# telakone-aux-gps.net
KiCad netlist of a schematic drawn in EAGLE
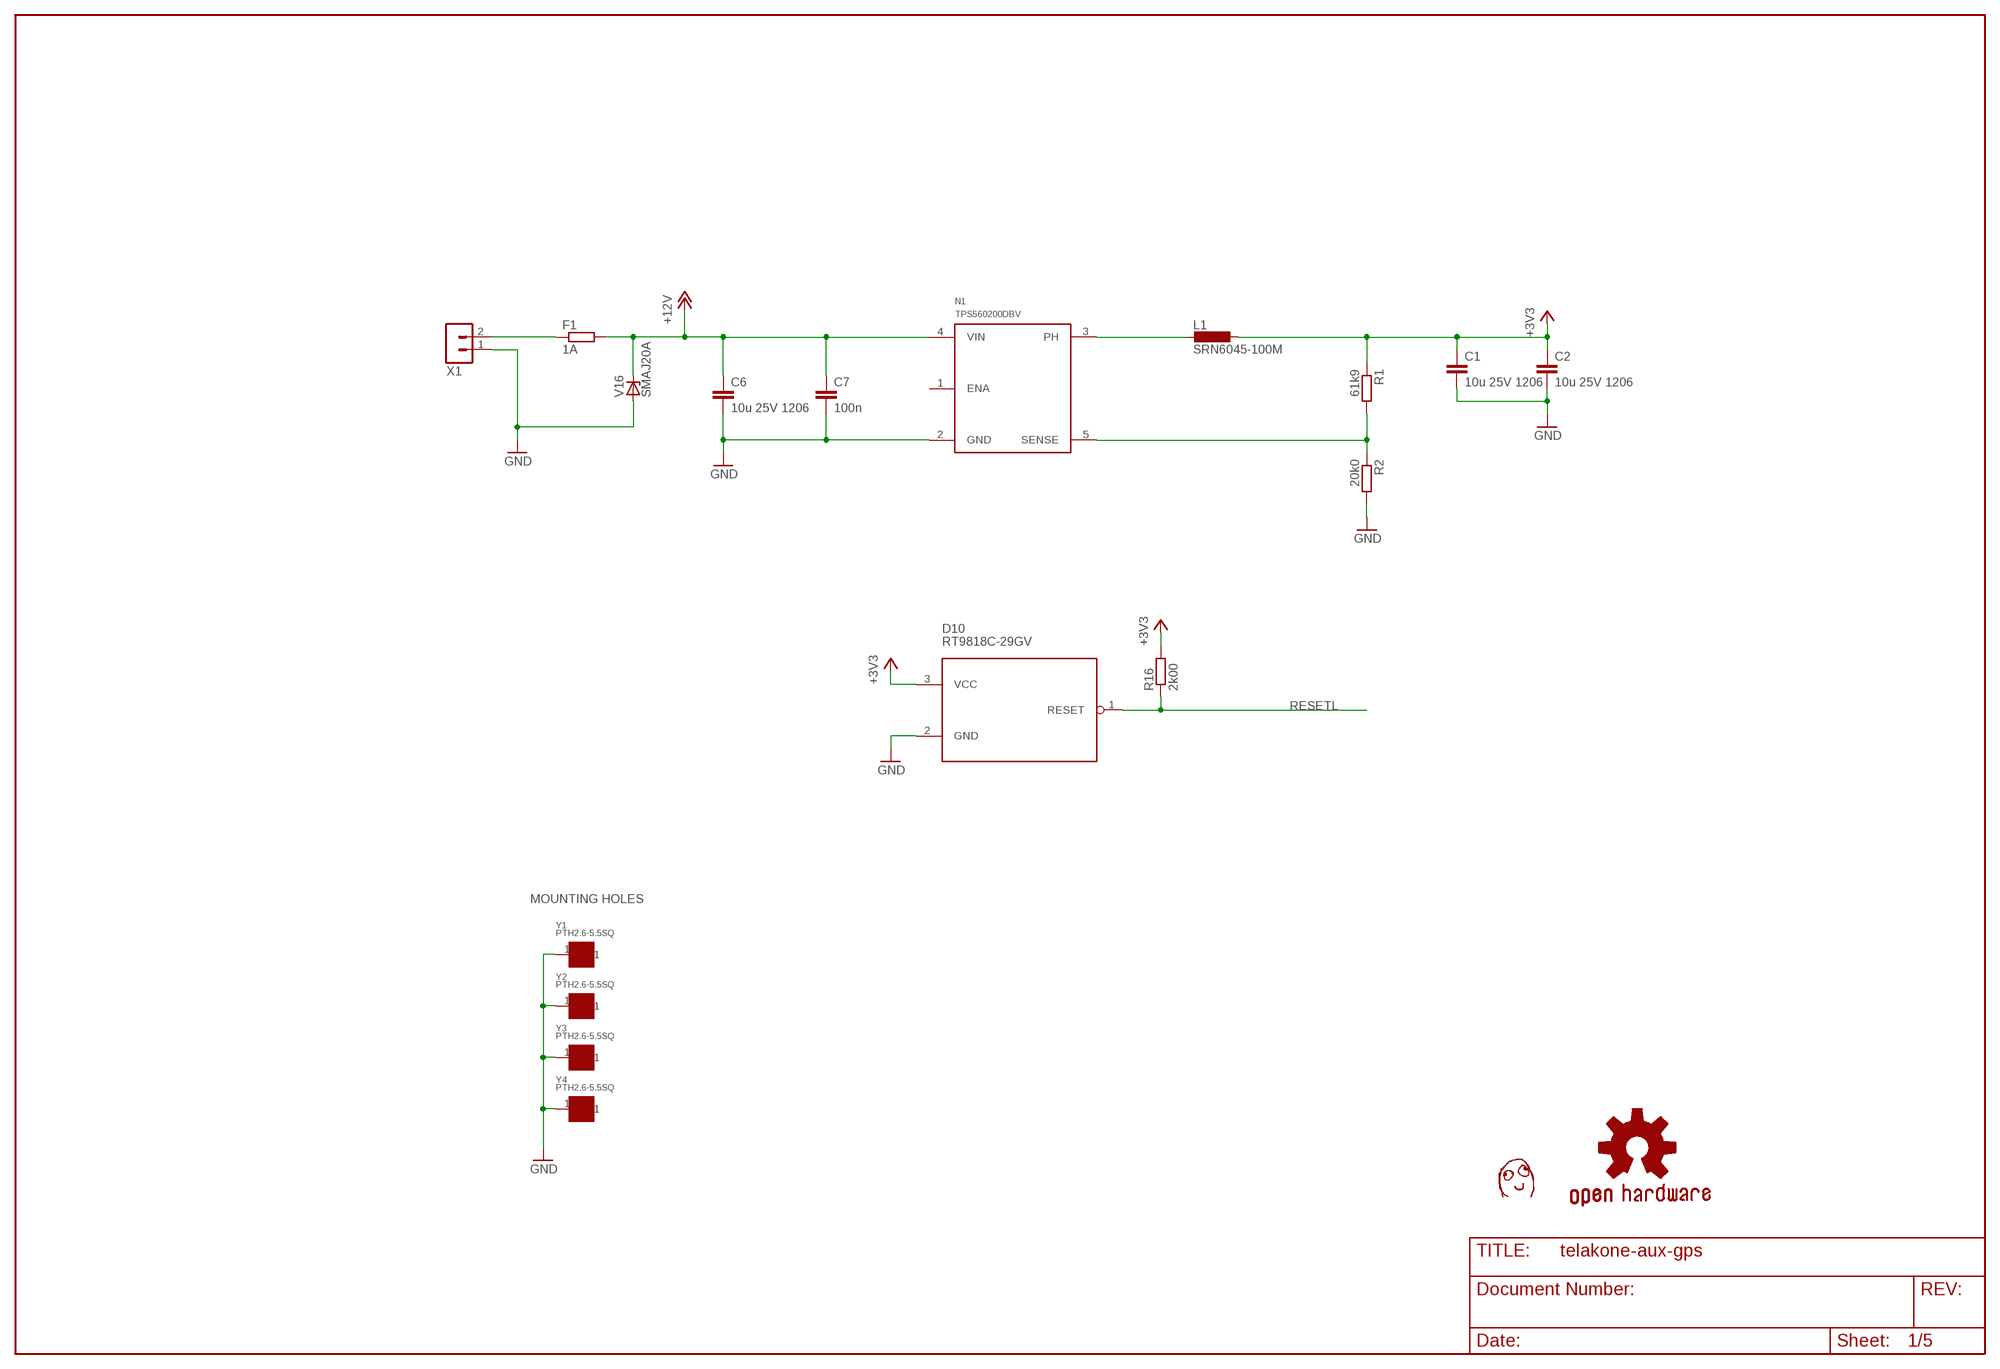
[diagram p0: schematic, sheet 1]
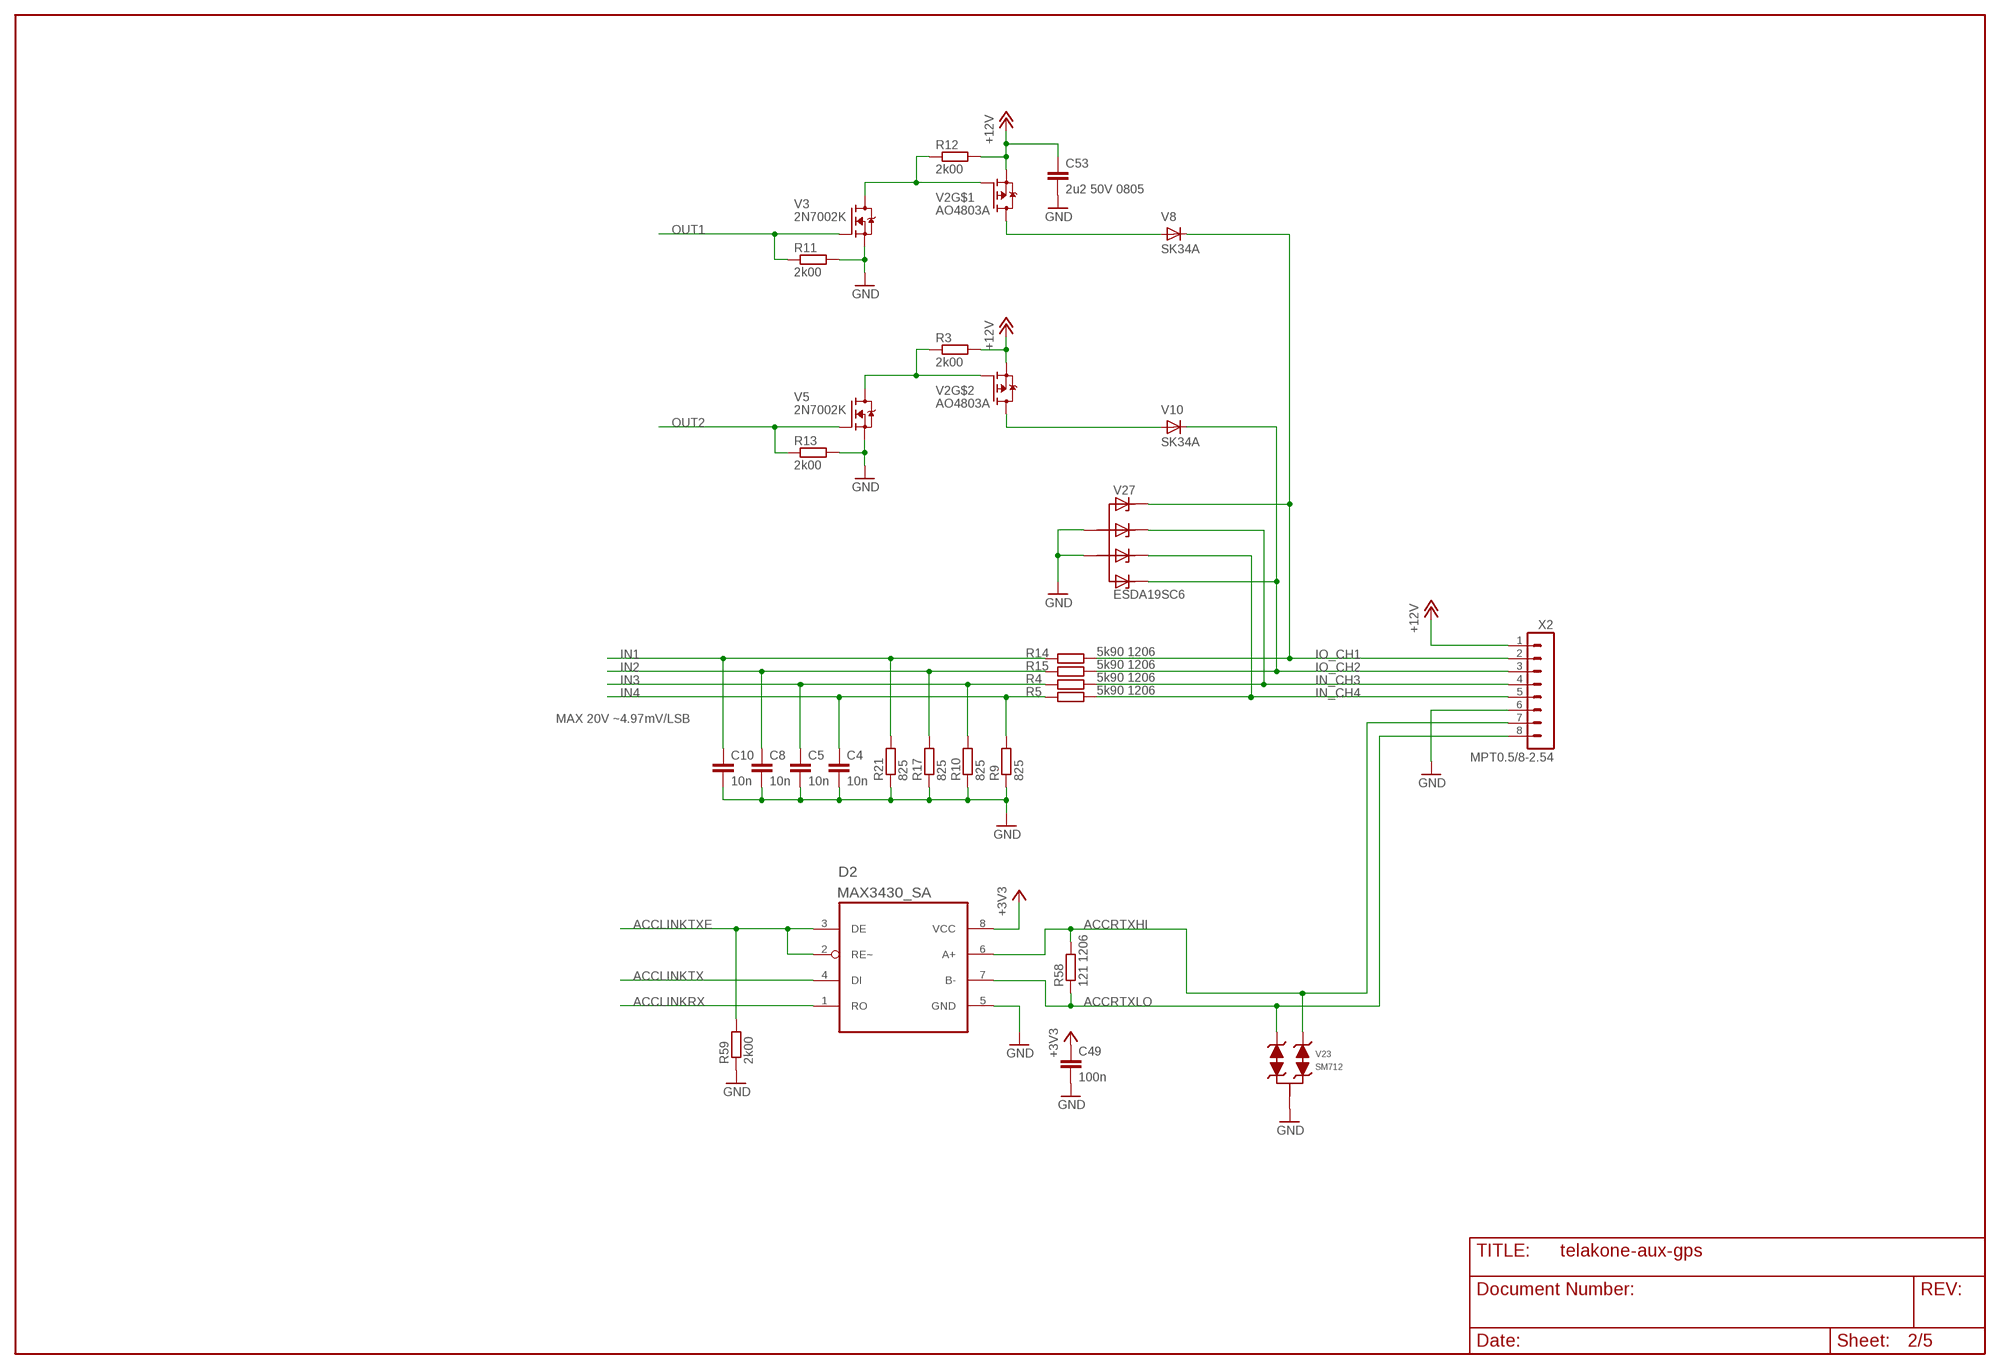
[diagram p1: schematic, sheet 2]
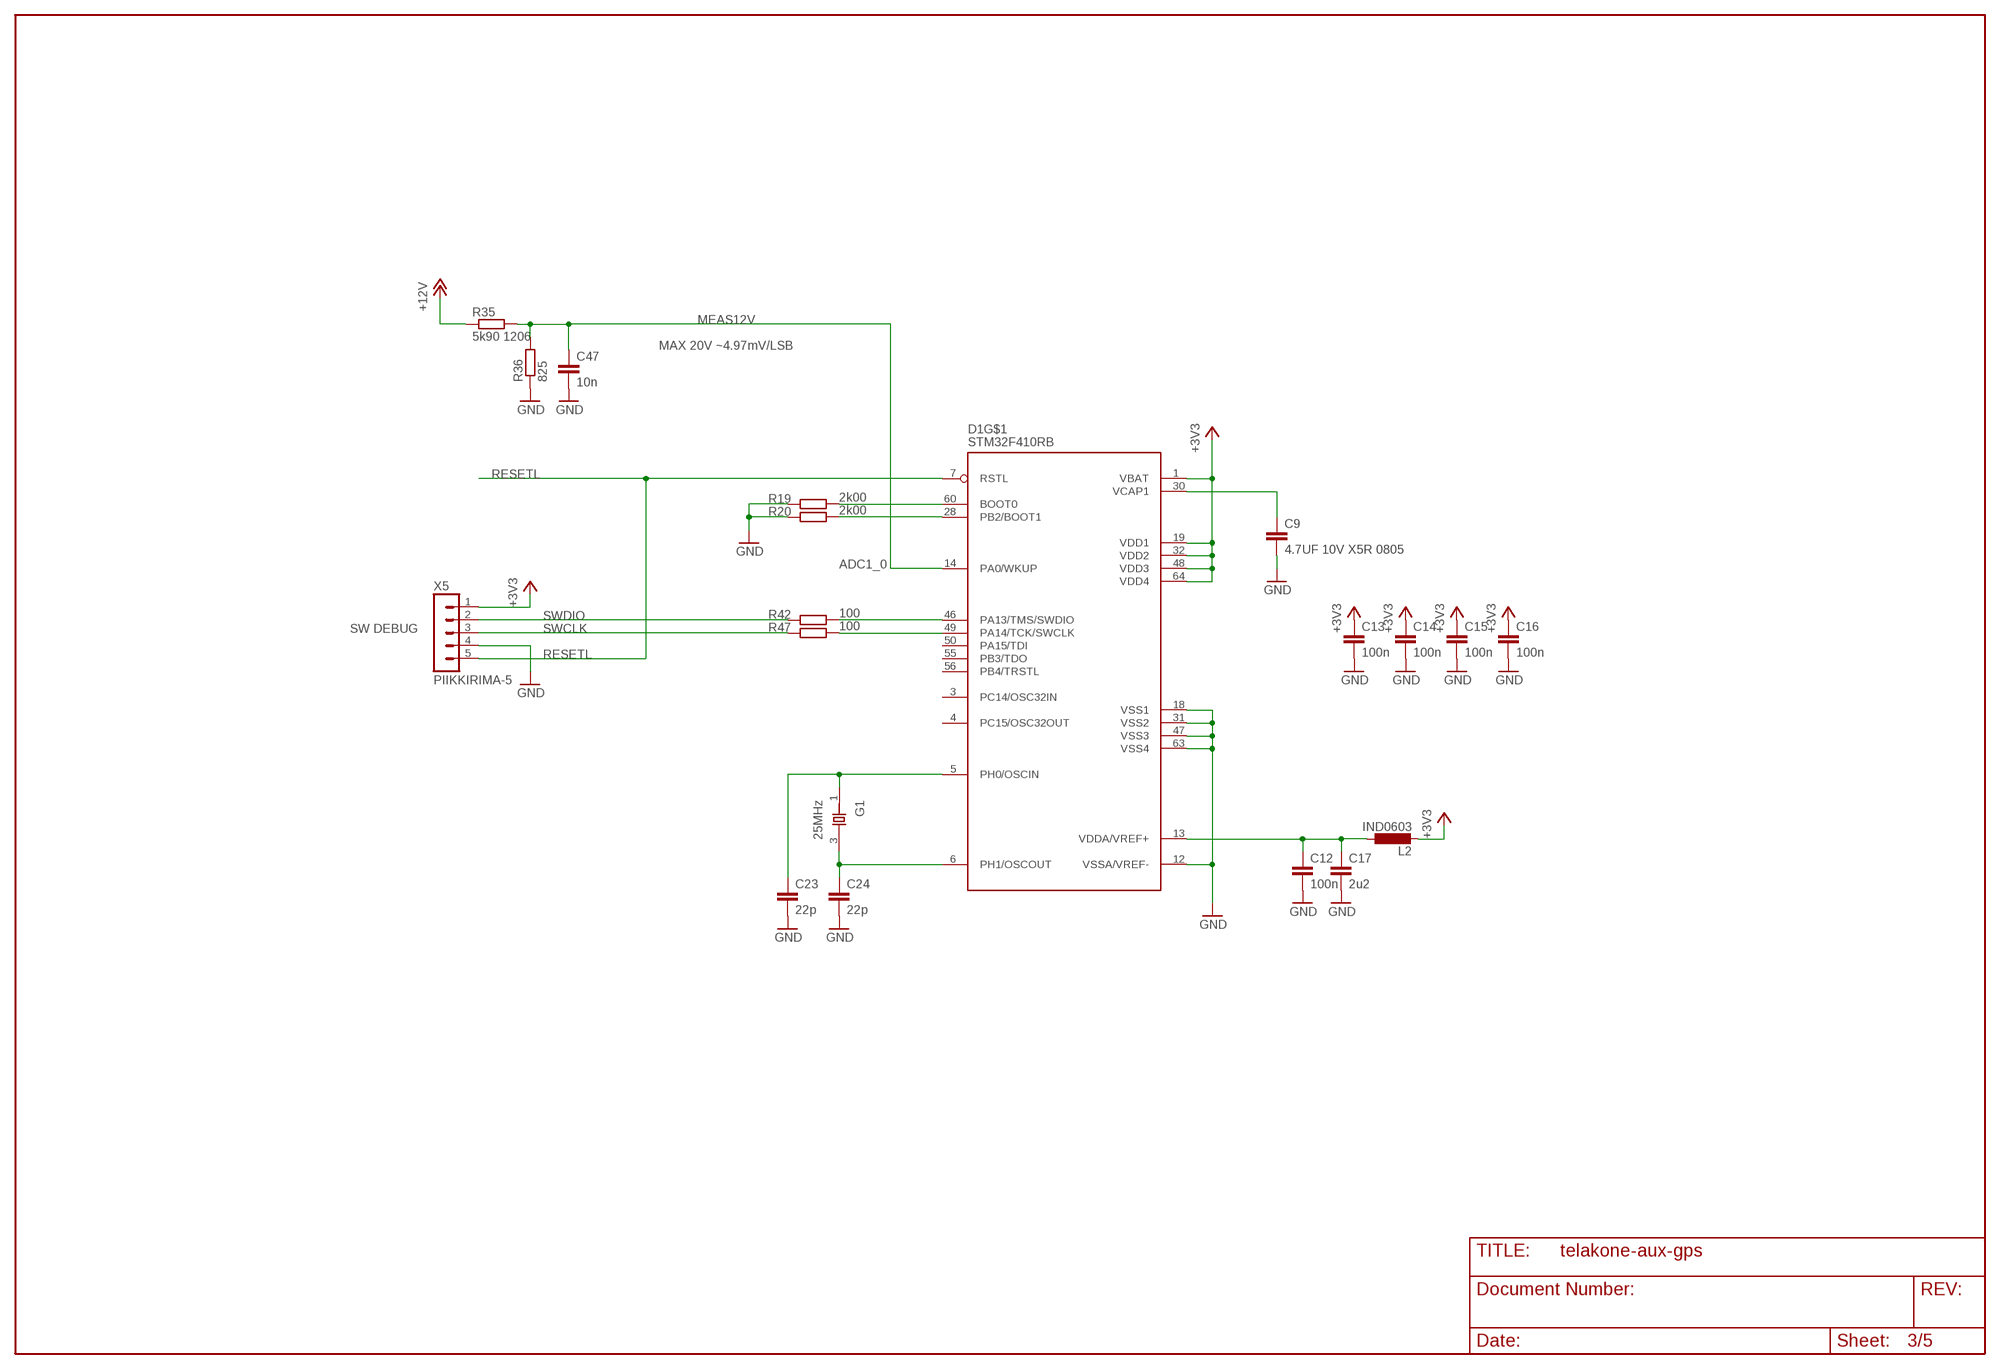
[diagram p2: schematic, sheet 3]
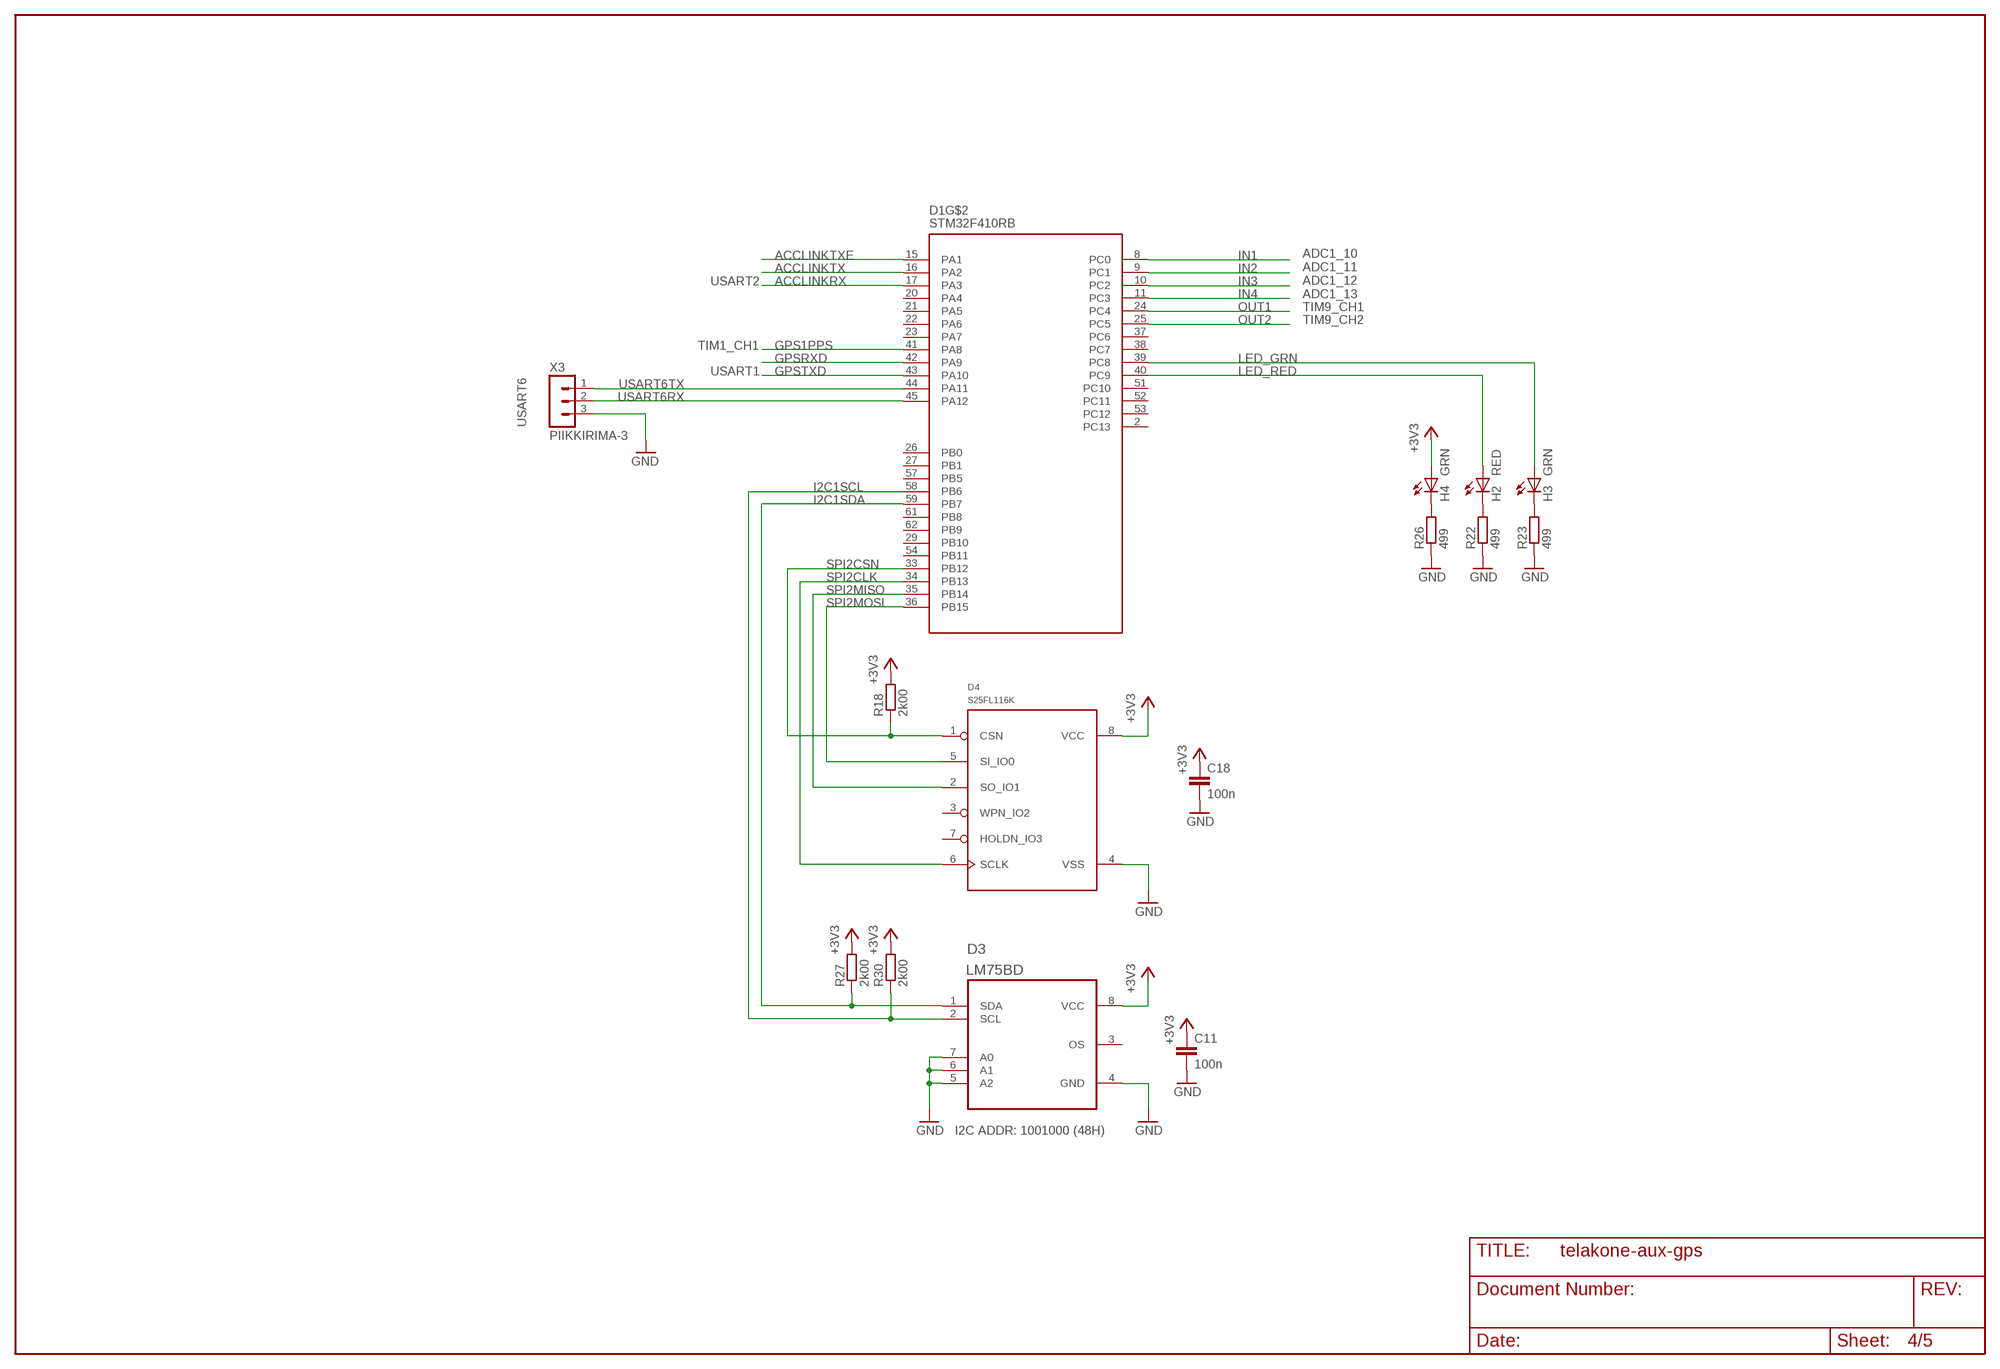
[diagram p3: schematic, sheet 4]
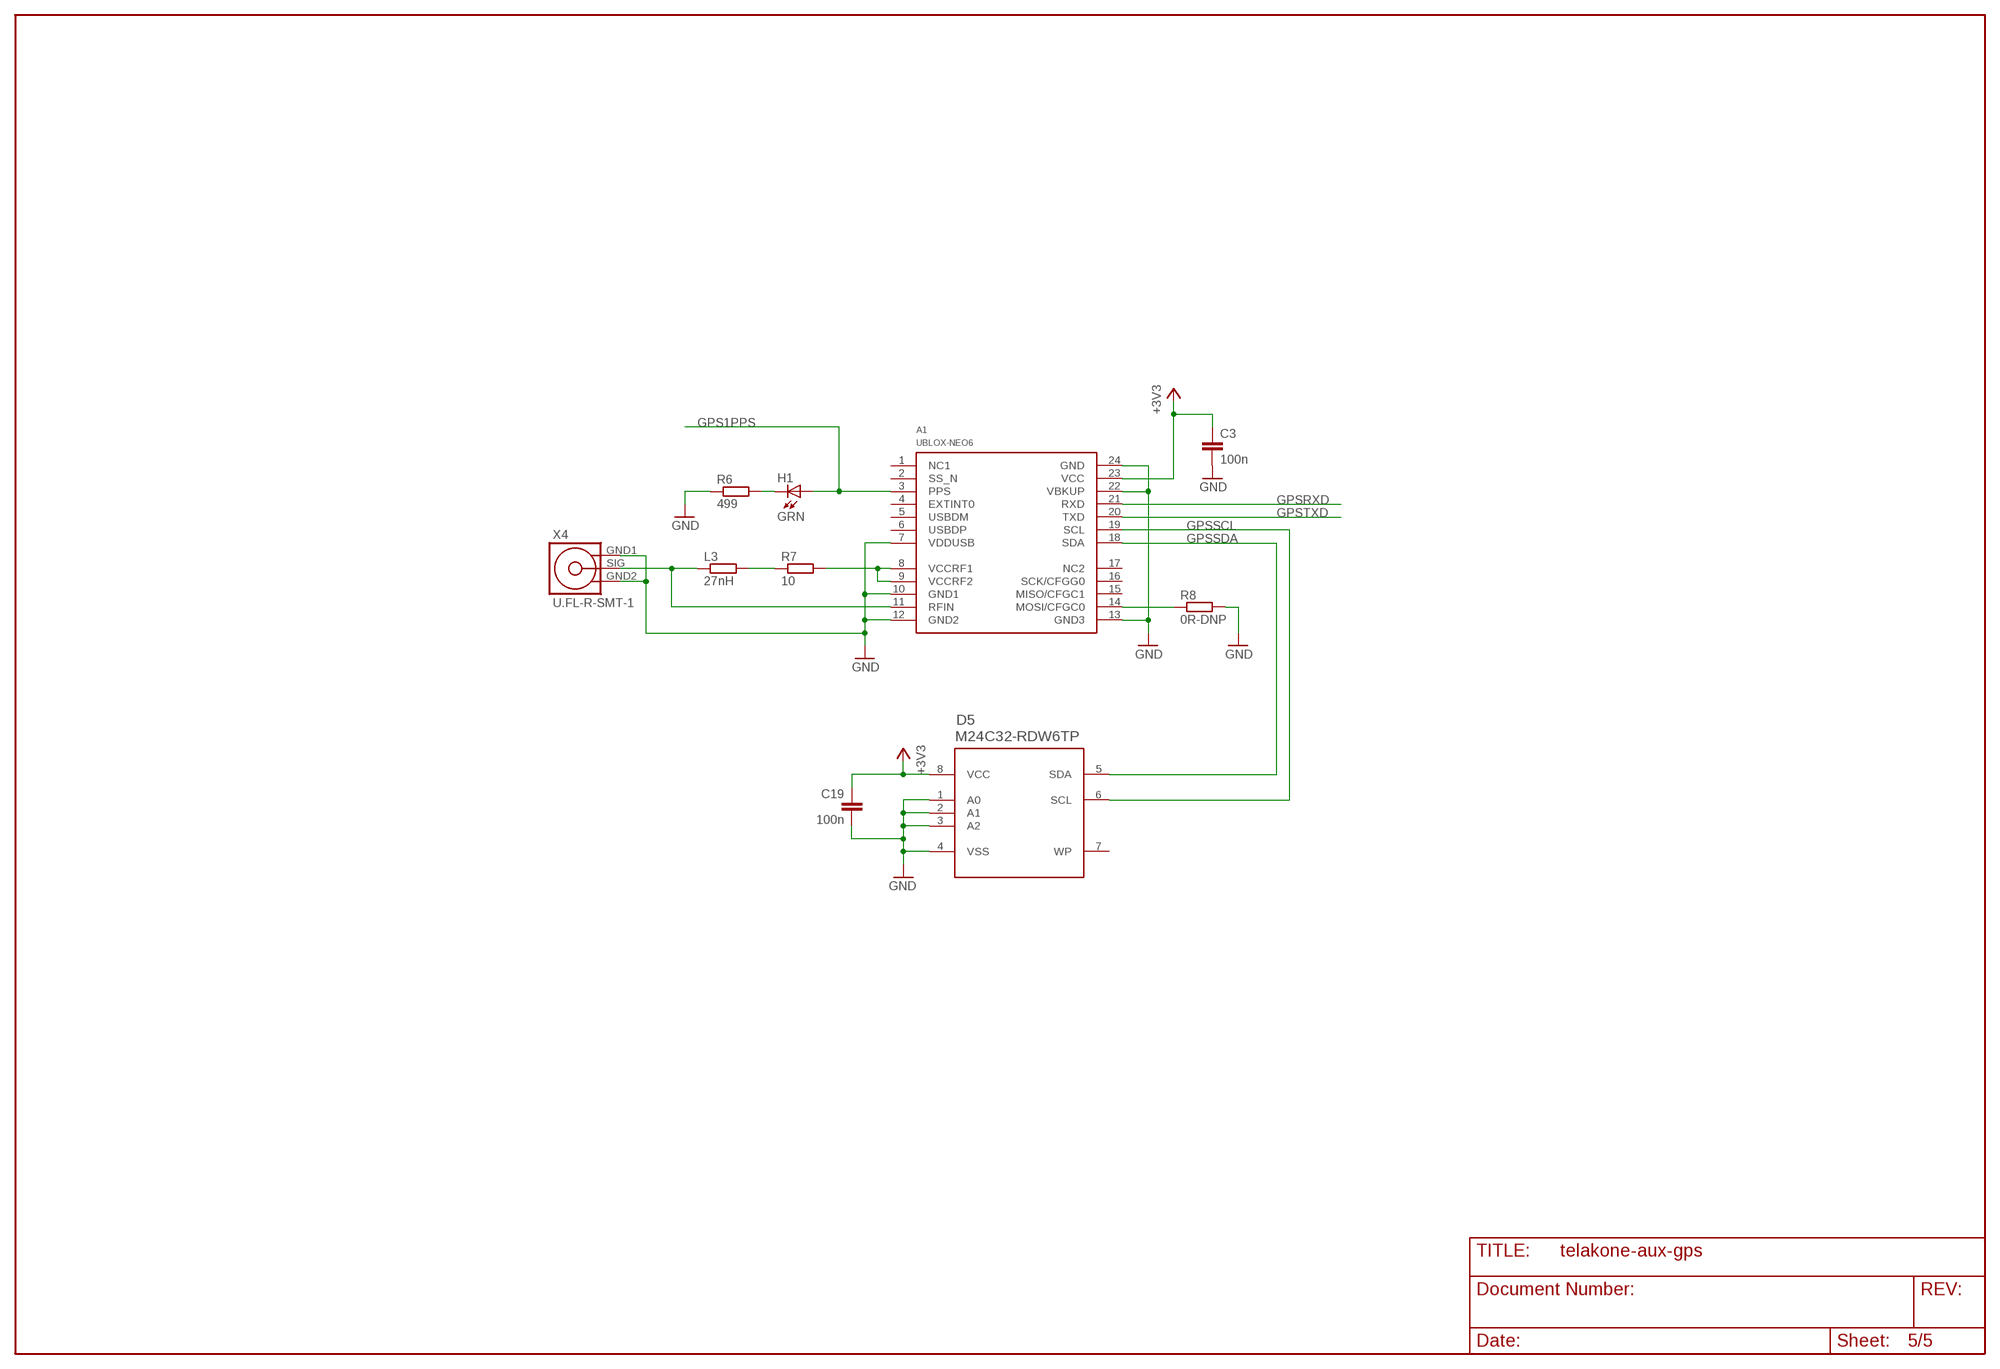
[diagram p4: schematic, sheet 5]

(export (version "E")
  (design (tool "Eeschema 10.0.6"))
  (components
    (comp (ref "C1")
      (value "10u 25V 1206")
      (footprint "eagle-import:C1206")
      (libsource (lib "eagle-import") (part "CAP1206"))
    )
    (comp (ref "C2")
      (value "10u 25V 1206")
      (footprint "eagle-import:C1206")
      (libsource (lib "eagle-import") (part "CAP1206"))
    )
    (comp (ref "C6")
      (value "10u 25V 1206")
      (footprint "eagle-import:C1206")
      (libsource (lib "eagle-import") (part "CAP1206"))
    )
    (comp (ref "C7")
      (value "100n")
      (footprint "eagle-import:C0603")
      (libsource (lib "eagle-import") (part "CAP0603"))
    )
    (comp (ref "D10")
      (value "RT9818C-29GV")
      (footprint "eagle-import:SOT23")
      (libsource (lib "eagle-import") (part "RT9818C-29GV"))
    )
    (comp (ref "F1")
      (value "1A")
      (footprint "eagle-import:R1206")
      (libsource (lib "eagle-import") (part "RES1206"))
    )
    (comp (ref "L1")
      (value "SRN6045-100M")
      (footprint "eagle-import:SRN6045")
      (libsource (lib "eagle-import") (part "SRN6045-100M"))
    )
    (comp (ref "N1")
      (value "TPS560200DBV")
      (footprint "eagle-import:SOT95P280X145-5N")
      (libsource (lib "eagle-import") (part "TPS560200DBV"))
    )
    (comp (ref "R1")
      (value "61k9")
      (footprint "eagle-import:R0603")
      (libsource (lib "eagle-import") (part "RES0603"))
    )
    (comp (ref "R2")
      (value "20k0")
      (footprint "eagle-import:R0603")
      (libsource (lib "eagle-import") (part "RES0603"))
    )
    (comp (ref "R16")
      (value "2k00")
      (footprint "eagle-import:R0603")
      (libsource (lib "eagle-import") (part "RES0603"))
    )
    (comp (ref "U$5")
      (value "DAFUG")
      (footprint "eagle-import:DAFUG")
      (libsource (lib "eagle-import") (part "DAFUG"))
    )
    (comp (ref "V16")
      (value "SMAJ20A")
      (footprint "eagle-import:DO214AC")
      (libsource (lib "eagle-import") (part "SMAJXXA"))
    )
    (comp (ref "X1")
      (value "TE_RUUVILIITIN2")
      (footprint "eagle-import:TE_RUUVILIITIN2")
      (libsource (lib "eagle-import") (part "TE_RUUVILIITIN2"))
    )
    (comp (ref "Y1")
      (value "PTH2.6-5.5SQ")
      (footprint "eagle-import:PTH-2.6-5.5SQ")
      (libsource (lib "eagle-import") (part "PTH2.6-5.5SQ"))
    )
    (comp (ref "Y2")
      (value "PTH2.6-5.5SQ")
      (footprint "eagle-import:PTH-2.6-5.5SQ")
      (libsource (lib "eagle-import") (part "PTH2.6-5.5SQ"))
    )
    (comp (ref "Y3")
      (value "PTH2.6-5.5SQ")
      (footprint "eagle-import:PTH-2.6-5.5SQ")
      (libsource (lib "eagle-import") (part "PTH2.6-5.5SQ"))
    )
    (comp (ref "Y4")
      (value "PTH2.6-5.5SQ")
      (footprint "eagle-import:PTH-2.6-5.5SQ")
      (libsource (lib "eagle-import") (part "PTH2.6-5.5SQ"))
    )
    (comp (ref "C4")
      (value "10n")
      (footprint "eagle-import:C0603")
      (libsource (lib "eagle-import") (part "CAP0603"))
    )
    (comp (ref "C5")
      (value "10n")
      (footprint "eagle-import:C0603")
      (libsource (lib "eagle-import") (part "CAP0603"))
    )
    (comp (ref "C8")
      (value "10n")
      (footprint "eagle-import:C0603")
      (libsource (lib "eagle-import") (part "CAP0603"))
    )
    (comp (ref "C10")
      (value "10n")
      (footprint "eagle-import:C0603")
      (libsource (lib "eagle-import") (part "CAP0603"))
    )
    (comp (ref "C49")
      (value "100n")
      (footprint "eagle-import:C0603")
      (libsource (lib "eagle-import") (part "CAP0603"))
    )
    (comp (ref "C53")
      (value "2u2 50V 0805")
      (footprint "eagle-import:C0805")
      (libsource (lib "eagle-import") (part "CAP0805"))
    )
    (comp (ref "D2")
      (value "MAX3430_SA")
      (footprint "eagle-import:SOIC8-N_MC")
      (libsource (lib "eagle-import") (part "MAX3088_SA"))
    )
    (comp (ref "R3")
      (value "2k00")
      (footprint "eagle-import:R0603")
      (libsource (lib "eagle-import") (part "RES0603"))
    )
    (comp (ref "R4")
      (value "5k90 1206")
      (footprint "eagle-import:R1206")
      (libsource (lib "eagle-import") (part "RES1206"))
    )
    (comp (ref "R5")
      (value "5k90 1206")
      (footprint "eagle-import:R1206")
      (libsource (lib "eagle-import") (part "RES1206"))
    )
    (comp (ref "R9")
      (value "825")
      (footprint "eagle-import:R0603")
      (libsource (lib "eagle-import") (part "RES0603"))
    )
    (comp (ref "R10")
      (value "825")
      (footprint "eagle-import:R0603")
      (libsource (lib "eagle-import") (part "RES0603"))
    )
    (comp (ref "R11")
      (value "2k00")
      (footprint "eagle-import:R0603")
      (libsource (lib "eagle-import") (part "RES0603"))
    )
    (comp (ref "R12")
      (value "2k00")
      (footprint "eagle-import:R0603")
      (libsource (lib "eagle-import") (part "RES0603"))
    )
    (comp (ref "R13")
      (value "2k00")
      (footprint "eagle-import:R0603")
      (libsource (lib "eagle-import") (part "RES0603"))
    )
    (comp (ref "R14")
      (value "5k90 1206")
      (footprint "eagle-import:R1206")
      (libsource (lib "eagle-import") (part "RES1206"))
    )
    (comp (ref "R15")
      (value "5k90 1206")
      (footprint "eagle-import:R1206")
      (libsource (lib "eagle-import") (part "RES1206"))
    )
    (comp (ref "R17")
      (value "825")
      (footprint "eagle-import:R0603")
      (libsource (lib "eagle-import") (part "RES0603"))
    )
    (comp (ref "R21")
      (value "825")
      (footprint "eagle-import:R0603")
      (libsource (lib "eagle-import") (part "RES0603"))
    )
    (comp (ref "R58")
      (value "121 1206")
      (footprint "eagle-import:R1206")
      (libsource (lib "eagle-import") (part "RES1206"))
    )
    (comp (ref "R59")
      (value "2k00")
      (footprint "eagle-import:R0603")
      (libsource (lib "eagle-import") (part "RES0603"))
    )
    (comp (ref "V2")
      (value "AO4803A")
      (footprint "eagle-import:SOIC8-N_MC")
      (libsource (lib "eagle-import") (part "AO4803A"))
    )
    (comp (ref "V3")
      (value "2N7002K")
      (footprint "eagle-import:SOT23")
      (libsource (lib "eagle-import") (part "2N7002K"))
    )
    (comp (ref "V5")
      (value "2N7002K")
      (footprint "eagle-import:SOT23")
      (libsource (lib "eagle-import") (part "2N7002K"))
    )
    (comp (ref "V8")
      (value "SK34A")
      (footprint "eagle-import:DO214AC")
      (libsource (lib "eagle-import") (part "SK34A"))
    )
    (comp (ref "V10")
      (value "SK34A")
      (footprint "eagle-import:DO214AC")
      (libsource (lib "eagle-import") (part "SK34A"))
    )
    (comp (ref "V23")
      (value "SM712")
      (footprint "eagle-import:SOT23")
      (libsource (lib "eagle-import") (part "SM712"))
    )
    (comp (ref "V27")
      (value "ESDA19SC6")
      (footprint "eagle-import:SOT23-6")
      (libsource (lib "eagle-import") (part "ESDAXXSC6"))
    )
    (comp (ref "X2")
      (value "MPT0.5/8-2.54")
      (footprint "eagle-import:MPT0.5_8-2.54")
      (libsource (lib "eagle-import") (part "MPT0.5/8-2.54"))
    )
    (comp (ref "C11")
      (value "100n")
      (footprint "eagle-import:C0603")
      (libsource (lib "eagle-import") (part "CAP0603"))
    )
    (comp (ref "C18")
      (value "100n")
      (footprint "eagle-import:C0603")
      (libsource (lib "eagle-import") (part "CAP0603"))
    )
    (comp (ref "D1")
      (value "STM32F410RB")
      (footprint "eagle-import:LQFP-64")
      (libsource (lib "eagle-import") (part "STM32F410RB"))
    )
    (comp (ref "D3")
      (value "LM75BD")
      (footprint "eagle-import:SOIC8-N_MC")
      (libsource (lib "eagle-import") (part "LM75BD"))
    )
    (comp (ref "D4")
      (value "S25FL116K")
      (footprint "eagle-import:SOIC8-N_MC")
      (libsource (lib "eagle-import") (part "S25FL116K"))
    )
    (comp (ref "H2")
      (value "RED")
      (footprint "eagle-import:CHIP-LED0603")
      (libsource (lib "eagle-import") (part "LEDCHIP-LED0603"))
    )
    (comp (ref "H3")
      (value "GRN")
      (footprint "eagle-import:CHIP-LED0603")
      (libsource (lib "eagle-import") (part "LEDCHIP-LED0603"))
    )
    (comp (ref "H4")
      (value "GRN")
      (footprint "eagle-import:CHIP-LED0603")
      (libsource (lib "eagle-import") (part "LEDCHIP-LED0603"))
    )
    (comp (ref "R18")
      (value "2k00")
      (footprint "eagle-import:R0603")
      (libsource (lib "eagle-import") (part "RES0603"))
    )
    (comp (ref "R22")
      (value "499")
      (footprint "eagle-import:R0603")
      (libsource (lib "eagle-import") (part "RES0603"))
    )
    (comp (ref "R23")
      (value "499")
      (footprint "eagle-import:R0603")
      (libsource (lib "eagle-import") (part "RES0603"))
    )
    (comp (ref "R26")
      (value "499")
      (footprint "eagle-import:R0603")
      (libsource (lib "eagle-import") (part "RES0603"))
    )
    (comp (ref "R27")
      (value "2k00")
      (footprint "eagle-import:R0603")
      (libsource (lib "eagle-import") (part "RES0603"))
    )
    (comp (ref "R30")
      (value "2k00")
      (footprint "eagle-import:R0603")
      (libsource (lib "eagle-import") (part "RES0603"))
    )
    (comp (ref "X3")
      (value "PIIKKIRIMA-3")
      (footprint "eagle-import:PIIKKIRIMA-3")
      (libsource (lib "eagle-import") (part "PIIKKIRIMA-3"))
    )
    (comp (ref "C9")
      (value "4.7UF 10V X5R 0805")
      (footprint "eagle-import:C0805")
      (libsource (lib "eagle-import") (part "CAP0805"))
    )
    (comp (ref "C12")
      (value "100n")
      (footprint "eagle-import:C0603")
      (libsource (lib "eagle-import") (part "CAP0603"))
    )
    (comp (ref "C13")
      (value "100n")
      (footprint "eagle-import:C0603")
      (libsource (lib "eagle-import") (part "CAP0603"))
    )
    (comp (ref "C14")
      (value "100n")
      (footprint "eagle-import:C0603")
      (libsource (lib "eagle-import") (part "CAP0603"))
    )
    (comp (ref "C15")
      (value "100n")
      (footprint "eagle-import:C0603")
      (libsource (lib "eagle-import") (part "CAP0603"))
    )
    (comp (ref "C16")
      (value "100n")
      (footprint "eagle-import:C0603")
      (libsource (lib "eagle-import") (part "CAP0603"))
    )
    (comp (ref "C17")
      (value "2u2")
      (footprint "eagle-import:C0603")
      (libsource (lib "eagle-import") (part "CAP0603"))
    )
    (comp (ref "C23")
      (value "22p")
      (footprint "eagle-import:C0603")
      (libsource (lib "eagle-import") (part "CAP0603"))
    )
    (comp (ref "C24")
      (value "22p")
      (footprint "eagle-import:C0603")
      (libsource (lib "eagle-import") (part "CAP0603"))
    )
    (comp (ref "C47")
      (value "10n")
      (footprint "eagle-import:C0603")
      (libsource (lib "eagle-import") (part "CAP0603"))
    )
    (comp (ref "G1")
      (value "25MHz")
      (footprint "eagle-import:X_3225")
      (libsource (lib "eagle-import") (part "XTAL_3225_SMD"))
    )
    (comp (ref "L2")
      (value "IND0603")
      (footprint "eagle-import:R0603")
      (libsource (lib "eagle-import") (part "IND0603"))
    )
    (comp (ref "R19")
      (value "2k00")
      (footprint "eagle-import:R0603")
      (libsource (lib "eagle-import") (part "RES0603"))
    )
    (comp (ref "R20")
      (value "2k00")
      (footprint "eagle-import:R0603")
      (libsource (lib "eagle-import") (part "RES0603"))
    )
    (comp (ref "R35")
      (value "5k90 1206")
      (footprint "eagle-import:R1206")
      (libsource (lib "eagle-import") (part "RES1206"))
    )
    (comp (ref "R36")
      (value "825")
      (footprint "eagle-import:R0603")
      (libsource (lib "eagle-import") (part "RES0603"))
    )
    (comp (ref "R42")
      (value "100")
      (footprint "eagle-import:R0603")
      (libsource (lib "eagle-import") (part "RES0603"))
    )
    (comp (ref "R47")
      (value "100")
      (footprint "eagle-import:R0603")
      (libsource (lib "eagle-import") (part "RES0603"))
    )
    (comp (ref "X5")
      (value "PIIKKIRIMA-5")
      (footprint "eagle-import:PIIKKIRIMA-5")
      (libsource (lib "eagle-import") (part "PIIKKIRIMA-5"))
    )
    (comp (ref "A1")
      (value "UBLOX-NEO6")
      (footprint "eagle-import:UBLOX-NEO6")
      (libsource (lib "eagle-import") (part "UBLOX-NEO6"))
    )
    (comp (ref "C3")
      (value "100n")
      (footprint "eagle-import:C0603")
      (libsource (lib "eagle-import") (part "CAP0603"))
    )
    (comp (ref "C19")
      (value "100n")
      (footprint "eagle-import:C0603")
      (libsource (lib "eagle-import") (part "CAP0603"))
    )
    (comp (ref "D5")
      (value "M24C32-RDW6TP")
      (footprint "eagle-import:TSSOP8-66")
      (libsource (lib "eagle-import") (part "M24C32-RDW6TP"))
    )
    (comp (ref "H1")
      (value "GRN")
      (footprint "eagle-import:CHIP-LED0603")
      (libsource (lib "eagle-import") (part "LEDCHIP-LED0603"))
    )
    (comp (ref "L3")
      (value "27nH")
      (footprint "eagle-import:R0603")
      (libsource (lib "eagle-import") (part "RES0603"))
    )
    (comp (ref "R6")
      (value "499")
      (footprint "eagle-import:R0603")
      (libsource (lib "eagle-import") (part "RES0603"))
    )
    (comp (ref "R7")
      (value "10")
      (footprint "eagle-import:R0603")
      (libsource (lib "eagle-import") (part "RES0603"))
    )
    (comp (ref "R8")
      (value "0R-DNP")
      (footprint "eagle-import:R0603")
      (libsource (lib "eagle-import") (part "RES0603"))
    )
    (comp (ref "X4")
      (value "U.FL-R-SMT-1")
      (footprint "eagle-import:U.FL-R-SMT-1")
      (libsource (lib "eagle-import") (part "U.FL-R-SMT-1"))
    )
  )
  (nets
    (net (code "1") (name "+3V3") (class "Default")
      (node (ref "A1") (pin "23") (pinfunction "VCC_23") (pintype "bidirectional"))
      (node (ref "C1") (pin "1") (pinfunction "1_1") (pintype "passive"))
      (node (ref "C11") (pin "1") (pinfunction "1_1") (pintype "passive"))
      (node (ref "C13") (pin "1") (pinfunction "1_1") (pintype "passive"))
      (node (ref "C14") (pin "1") (pinfunction "1_1") (pintype "passive"))
      (node (ref "C15") (pin "1") (pinfunction "1_1") (pintype "passive"))
      (node (ref "C16") (pin "1") (pinfunction "1_1") (pintype "passive"))
      (node (ref "C18") (pin "1") (pinfunction "1_1") (pintype "passive"))
      (node (ref "C19") (pin "1") (pinfunction "1_1") (pintype "passive"))
      (node (ref "C2") (pin "1") (pinfunction "1_1") (pintype "passive"))
      (node (ref "C3") (pin "1") (pinfunction "1_1") (pintype "passive"))
      (node (ref "C49") (pin "1") (pinfunction "1_1") (pintype "passive"))
      (node (ref "D1") (pin "1") (pinfunction "VBAT_1") (pintype "bidirectional"))
      (node (ref "D1") (pin "19") (pinfunction "VDD1_19") (pintype "bidirectional"))
      (node (ref "D1") (pin "32") (pinfunction "VDD2_32") (pintype "bidirectional"))
      (node (ref "D1") (pin "48") (pinfunction "VDD3_48") (pintype "bidirectional"))
      (node (ref "D1") (pin "64") (pinfunction "VDD4_64") (pintype "bidirectional"))
      (node (ref "D10") (pin "3") (pinfunction "VCC_3") (pintype "bidirectional"))
      (node (ref "D2") (pin "8") (pinfunction "VCC_8") (pintype "power_in"))
      (node (ref "D3") (pin "8") (pinfunction "VCC_8") (pintype "bidirectional"))
      (node (ref "D4") (pin "8") (pinfunction "VCC_8") (pintype "bidirectional"))
      (node (ref "D5") (pin "8") (pinfunction "VCC_8") (pintype "power_in"))
      (node (ref "H4") (pin "A") (pinfunction "A_A") (pintype "passive"))
      (node (ref "L1") (pin "1") (pinfunction "1_1") (pintype "passive"))
      (node (ref "L2") (pin "2") (pinfunction "2_2") (pintype "passive"))
      (node (ref "R1") (pin "1") (pinfunction "1_1") (pintype "passive"))
      (node (ref "R16") (pin "2") (pinfunction "2_2") (pintype "passive"))
      (node (ref "R18") (pin "2") (pinfunction "2_2") (pintype "passive"))
      (node (ref "R27") (pin "2") (pinfunction "2_2") (pintype "passive"))
      (node (ref "R30") (pin "2") (pinfunction "2_2") (pintype "passive"))
      (node (ref "X5") (pin "1") (pinfunction "1_1") (pintype "passive"))
    )
    (net (code "2") (name "+12V") (class "Default")
      (node (ref "C53") (pin "1") (pinfunction "1_1") (pintype "passive"))
      (node (ref "C6") (pin "1") (pinfunction "1_1") (pintype "passive"))
      (node (ref "C7") (pin "1") (pinfunction "1_1") (pintype "passive"))
      (node (ref "F1") (pin "2") (pinfunction "2_2") (pintype "passive"))
      (node (ref "N1") (pin "4") (pinfunction "VIN_4") (pintype "bidirectional"))
      (node (ref "R12") (pin "2") (pinfunction "2_2") (pintype "passive"))
      (node (ref "R3") (pin "2") (pinfunction "2_2") (pintype "passive"))
      (node (ref "R35") (pin "1") (pinfunction "1_1") (pintype "passive"))
      (node (ref "V16") (pin "C") (pinfunction "C_C") (pintype "passive"))
      (node (ref "V2") (pin "1") (pinfunction "S_1") (pintype "passive"))
      (node (ref "V2") (pin "3") (pinfunction "S_3") (pintype "passive"))
      (node (ref "X2") (pin "1") (pinfunction "1_1") (pintype "passive"))
    )
    (net (code "3") (name "ACCLINKRX") (class "Default")
      (node (ref "D1") (pin "17") (pinfunction "PA3_17") (pintype "bidirectional"))
      (node (ref "D2") (pin "1") (pinfunction "RO_1") (pintype "output"))
    )
    (net (code "4") (name "ACCLINKTX") (class "Default")
      (node (ref "D1") (pin "16") (pinfunction "PA2_16") (pintype "bidirectional"))
      (node (ref "D2") (pin "4") (pinfunction "DI_4") (pintype "input"))
    )
    (net (code "5") (name "ACCLINKTXE") (class "Default")
      (node (ref "D1") (pin "15") (pinfunction "PA1_15") (pintype "bidirectional"))
      (node (ref "D2") (pin "2") (pinfunction "RE~{}_2") (pintype "input"))
      (node (ref "D2") (pin "3") (pinfunction "DE_3") (pintype "input"))
      (node (ref "R59") (pin "2") (pinfunction "2_2") (pintype "passive"))
    )
    (net (code "6") (name "ACCRTXHI") (class "Default")
      (node (ref "D2") (pin "6") (pinfunction "A+_6") (pintype "bidirectional"))
      (node (ref "R58") (pin "2") (pinfunction "2_2") (pintype "passive"))
      (node (ref "V23") (pin "1") (pinfunction "1_1") (pintype "bidirectional"))
      (node (ref "X2") (pin "7") (pinfunction "7_7") (pintype "passive"))
    )
    (net (code "7") (name "ACCRTXLO") (class "Default")
      (node (ref "D2") (pin "7") (pinfunction "B-_7") (pintype "bidirectional"))
      (node (ref "R58") (pin "1") (pinfunction "1_1") (pintype "passive"))
      (node (ref "V23") (pin "2") (pinfunction "2_2") (pintype "bidirectional"))
      (node (ref "X2") (pin "8") (pinfunction "8_8") (pintype "passive"))
    )
    (net (code "8") (name "GND") (class "Default")
      (node (ref "A1") (pin "10") (pinfunction "GND1_10") (pintype "bidirectional"))
      (node (ref "A1") (pin "12") (pinfunction "GND2_12") (pintype "bidirectional"))
      (node (ref "A1") (pin "13") (pinfunction "GND3_13") (pintype "bidirectional"))
      (node (ref "A1") (pin "22") (pinfunction "VBKUP_22") (pintype "bidirectional"))
      (node (ref "A1") (pin "24") (pinfunction "GND_24") (pintype "bidirectional"))
      (node (ref "A1") (pin "7") (pinfunction "VDDUSB_7") (pintype "bidirectional"))
      (node (ref "C1") (pin "2") (pinfunction "2_2") (pintype "passive"))
      (node (ref "C10") (pin "2") (pinfunction "2_2") (pintype "passive"))
      (node (ref "C11") (pin "2") (pinfunction "2_2") (pintype "passive"))
      (node (ref "C12") (pin "2") (pinfunction "2_2") (pintype "passive"))
      (node (ref "C13") (pin "2") (pinfunction "2_2") (pintype "passive"))
      (node (ref "C14") (pin "2") (pinfunction "2_2") (pintype "passive"))
      (node (ref "C15") (pin "2") (pinfunction "2_2") (pintype "passive"))
      (node (ref "C16") (pin "2") (pinfunction "2_2") (pintype "passive"))
      (node (ref "C17") (pin "2") (pinfunction "2_2") (pintype "passive"))
      (node (ref "C18") (pin "2") (pinfunction "2_2") (pintype "passive"))
      (node (ref "C19") (pin "2") (pinfunction "2_2") (pintype "passive"))
      (node (ref "C2") (pin "2") (pinfunction "2_2") (pintype "passive"))
      (node (ref "C23") (pin "2") (pinfunction "2_2") (pintype "passive"))
      (node (ref "C24") (pin "2") (pinfunction "2_2") (pintype "passive"))
      (node (ref "C3") (pin "2") (pinfunction "2_2") (pintype "passive"))
      (node (ref "C4") (pin "2") (pinfunction "2_2") (pintype "passive"))
      (node (ref "C47") (pin "2") (pinfunction "2_2") (pintype "passive"))
      (node (ref "C49") (pin "2") (pinfunction "2_2") (pintype "passive"))
      (node (ref "C5") (pin "2") (pinfunction "2_2") (pintype "passive"))
      (node (ref "C53") (pin "2") (pinfunction "2_2") (pintype "passive"))
      (node (ref "C6") (pin "2") (pinfunction "2_2") (pintype "passive"))
      (node (ref "C7") (pin "2") (pinfunction "2_2") (pintype "passive"))
      (node (ref "C8") (pin "2") (pinfunction "2_2") (pintype "passive"))
      (node (ref "C9") (pin "2") (pinfunction "2_2") (pintype "passive"))
      (node (ref "D1") (pin "12") (pinfunction "VSSA/VREF-_12") (pintype "bidirectional"))
      (node (ref "D1") (pin "18") (pinfunction "VSS1_18") (pintype "bidirectional"))
      (node (ref "D1") (pin "31") (pinfunction "VSS2_31") (pintype "bidirectional"))
      (node (ref "D1") (pin "47") (pinfunction "VSS3_47") (pintype "bidirectional"))
      (node (ref "D1") (pin "63") (pinfunction "VSS4_63") (pintype "bidirectional"))
      (node (ref "D10") (pin "2") (pinfunction "GND_2") (pintype "bidirectional"))
      (node (ref "D2") (pin "5") (pinfunction "GND_5") (pintype "power_in"))
      (node (ref "D3") (pin "4") (pinfunction "GND_4") (pintype "input"))
      (node (ref "D3") (pin "5") (pinfunction "A2_5") (pintype "bidirectional"))
      (node (ref "D3") (pin "6") (pinfunction "A1_6") (pintype "bidirectional"))
      (node (ref "D3") (pin "7") (pinfunction "A0_7") (pintype "bidirectional"))
      (node (ref "D4") (pin "4") (pinfunction "VSS_4") (pintype "bidirectional"))
      (node (ref "D5") (pin "1") (pinfunction "A0_1") (pintype "power_in"))
      (node (ref "D5") (pin "2") (pinfunction "A1_2") (pintype "power_in"))
      (node (ref "D5") (pin "3") (pinfunction "A2_3") (pintype "power_in"))
      (node (ref "D5") (pin "4") (pinfunction "VSS_4") (pintype "passive"))
      (node (ref "N1") (pin "2") (pinfunction "GND_2") (pintype "bidirectional"))
      (node (ref "R10") (pin "1") (pinfunction "1_1") (pintype "passive"))
      (node (ref "R11") (pin "2") (pinfunction "2_2") (pintype "passive"))
      (node (ref "R13") (pin "2") (pinfunction "2_2") (pintype "passive"))
      (node (ref "R17") (pin "1") (pinfunction "1_1") (pintype "passive"))
      (node (ref "R19") (pin "1") (pinfunction "1_1") (pintype "passive"))
      (node (ref "R2") (pin "2") (pinfunction "2_2") (pintype "passive"))
      (node (ref "R20") (pin "1") (pinfunction "1_1") (pintype "passive"))
      (node (ref "R21") (pin "1") (pinfunction "1_1") (pintype "passive"))
      (node (ref "R22") (pin "1") (pinfunction "1_1") (pintype "passive"))
      (node (ref "R23") (pin "1") (pinfunction "1_1") (pintype "passive"))
      (node (ref "R26") (pin "1") (pinfunction "1_1") (pintype "passive"))
      (node (ref "R36") (pin "1") (pinfunction "1_1") (pintype "passive"))
      (node (ref "R59") (pin "1") (pinfunction "1_1") (pintype "passive"))
      (node (ref "R6") (pin "1") (pinfunction "1_1") (pintype "passive"))
      (node (ref "R8") (pin "2") (pinfunction "2_2") (pintype "passive"))
      (node (ref "R9") (pin "1") (pinfunction "1_1") (pintype "passive"))
      (node (ref "V16") (pin "A") (pinfunction "A_A") (pintype "passive"))
      (node (ref "V23") (pin "3") (pinfunction "3_3") (pintype "bidirectional"))
      (node (ref "V27") (pin "2") (pinfunction "A_2") (pintype "passive"))
      (node (ref "V27") (pin "5") (pinfunction "A1_5") (pintype "passive"))
      (node (ref "V3") (pin "2") (pinfunction "S_2") (pintype "passive"))
      (node (ref "V5") (pin "2") (pinfunction "S_2") (pintype "passive"))
      (node (ref "X1") (pin "1") (pinfunction "1_1") (pintype "passive"))
      (node (ref "X2") (pin "6") (pinfunction "6_6") (pintype "passive"))
      (node (ref "X3") (pin "3") (pinfunction "3_3") (pintype "passive"))
      (node (ref "X4") (pin "GND1") (pinfunction "1_GND1") (pintype "passive"))
      (node (ref "X4") (pin "GND2") (pinfunction "3_GND2") (pintype "passive"))
      (node (ref "X5") (pin "4") (pinfunction "4_4") (pintype "passive"))
      (node (ref "Y1") (pin "1") (pinfunction "1_1") (pintype "bidirectional"))
      (node (ref "Y2") (pin "1") (pinfunction "1_1") (pintype "bidirectional"))
      (node (ref "Y3") (pin "1") (pinfunction "1_1") (pintype "bidirectional"))
      (node (ref "Y4") (pin "1") (pinfunction "1_1") (pintype "bidirectional"))
    )
    (net (code "9") (name "GPS1PPS") (class "Default")
      (node (ref "A1") (pin "3") (pinfunction "PPS_3") (pintype "bidirectional"))
      (node (ref "D1") (pin "41") (pinfunction "PA8_41") (pintype "bidirectional"))
      (node (ref "H1") (pin "A") (pinfunction "A_A") (pintype "passive"))
    )
    (net (code "10") (name "GPSRXD") (class "Default")
      (node (ref "A1") (pin "21") (pinfunction "RXD_21") (pintype "bidirectional"))
      (node (ref "D1") (pin "42") (pinfunction "PA9_42") (pintype "bidirectional"))
    )
    (net (code "11") (name "GPSSCL") (class "Default")
      (node (ref "A1") (pin "19") (pinfunction "SCL_19") (pintype "bidirectional"))
      (node (ref "D5") (pin "6") (pinfunction "SCL_6") (pintype "input"))
    )
    (net (code "12") (name "GPSSDA") (class "Default")
      (node (ref "A1") (pin "18") (pinfunction "SDA_18") (pintype "bidirectional"))
      (node (ref "D5") (pin "5") (pinfunction "SDA_5") (pintype "bidirectional"))
    )
    (net (code "13") (name "GPSTXD") (class "Default")
      (node (ref "A1") (pin "20") (pinfunction "TXD_20") (pintype "bidirectional"))
      (node (ref "D1") (pin "43") (pinfunction "PA10_43") (pintype "bidirectional"))
    )
    (net (code "14") (name "I2C1SCL") (class "Default")
      (node (ref "D1") (pin "58") (pinfunction "PB6_58") (pintype "bidirectional"))
      (node (ref "D3") (pin "2") (pinfunction "SCL_2") (pintype "bidirectional"))
      (node (ref "R30") (pin "1") (pinfunction "1_1") (pintype "passive"))
    )
    (net (code "15") (name "I2C1SDA") (class "Default")
      (node (ref "D1") (pin "59") (pinfunction "PB7_59") (pintype "bidirectional"))
      (node (ref "D3") (pin "1") (pinfunction "SDA_1") (pintype "power_in"))
      (node (ref "R27") (pin "1") (pinfunction "1_1") (pintype "passive"))
    )
    (net (code "16") (name "IN1") (class "Default")
      (node (ref "C10") (pin "1") (pinfunction "1_1") (pintype "passive"))
      (node (ref "D1") (pin "8") (pinfunction "PC0_8") (pintype "bidirectional"))
      (node (ref "R14") (pin "1") (pinfunction "1_1") (pintype "passive"))
      (node (ref "R21") (pin "2") (pinfunction "2_2") (pintype "passive"))
    )
    (net (code "17") (name "IN2") (class "Default")
      (node (ref "C8") (pin "1") (pinfunction "1_1") (pintype "passive"))
      (node (ref "D1") (pin "9") (pinfunction "PC1_9") (pintype "bidirectional"))
      (node (ref "R15") (pin "1") (pinfunction "1_1") (pintype "passive"))
      (node (ref "R17") (pin "2") (pinfunction "2_2") (pintype "passive"))
    )
    (net (code "18") (name "IN3") (class "Default")
      (node (ref "C5") (pin "1") (pinfunction "1_1") (pintype "passive"))
      (node (ref "D1") (pin "10") (pinfunction "PC2_10") (pintype "bidirectional"))
      (node (ref "R10") (pin "2") (pinfunction "2_2") (pintype "passive"))
      (node (ref "R4") (pin "1") (pinfunction "1_1") (pintype "passive"))
    )
    (net (code "19") (name "IN4") (class "Default")
      (node (ref "C4") (pin "1") (pinfunction "1_1") (pintype "passive"))
      (node (ref "D1") (pin "11") (pinfunction "PC3_11") (pintype "bidirectional"))
      (node (ref "R5") (pin "1") (pinfunction "1_1") (pintype "passive"))
      (node (ref "R9") (pin "2") (pinfunction "2_2") (pintype "passive"))
    )
    (net (code "20") (name "IN_CH3") (class "Default")
      (node (ref "R4") (pin "2") (pinfunction "2_2") (pintype "passive"))
      (node (ref "V27") (pin "3") (pinfunction "C1_3") (pintype "passive"))
      (node (ref "X2") (pin "4") (pinfunction "4_4") (pintype "passive"))
    )
    (net (code "21") (name "IN_CH4") (class "Default")
      (node (ref "R5") (pin "2") (pinfunction "2_2") (pintype "passive"))
      (node (ref "V27") (pin "4") (pinfunction "C2_4") (pintype "passive"))
      (node (ref "X2") (pin "5") (pinfunction "5_5") (pintype "passive"))
    )
    (net (code "22") (name "IO_CH1") (class "Default")
      (node (ref "R14") (pin "2") (pinfunction "2_2") (pintype "passive"))
      (node (ref "V27") (pin "1") (pinfunction "C_1") (pintype "passive"))
      (node (ref "V8") (pin "C") (pinfunction "C_C") (pintype "passive"))
      (node (ref "X2") (pin "2") (pinfunction "2_2") (pintype "passive"))
    )
    (net (code "23") (name "IO_CH2") (class "Default")
      (node (ref "R15") (pin "2") (pinfunction "2_2") (pintype "passive"))
      (node (ref "V10") (pin "C") (pinfunction "C_C") (pintype "passive"))
      (node (ref "V27") (pin "6") (pinfunction "C3_6") (pintype "passive"))
      (node (ref "X2") (pin "3") (pinfunction "3_3") (pintype "passive"))
    )
    (net (code "24") (name "LED_GRN") (class "Default")
      (node (ref "D1") (pin "39") (pinfunction "PC8_39") (pintype "bidirectional"))
      (node (ref "H3") (pin "A") (pinfunction "A_A") (pintype "passive"))
    )
    (net (code "25") (name "LED_RED") (class "Default")
      (node (ref "D1") (pin "40") (pinfunction "PC9_40") (pintype "bidirectional"))
      (node (ref "H2") (pin "A") (pinfunction "A_A") (pintype "passive"))
    )
    (net (code "26") (name "MEAS12V") (class "Default")
      (node (ref "C47") (pin "1") (pinfunction "1_1") (pintype "passive"))
      (node (ref "D1") (pin "14") (pinfunction "PA0/WKUP_14") (pintype "bidirectional"))
      (node (ref "R35") (pin "2") (pinfunction "2_2") (pintype "passive"))
      (node (ref "R36") (pin "2") (pinfunction "2_2") (pintype "passive"))
    )
    (net (code "27") (name "Net-(A1-MOSI{slash}CFGC0)") (class "Default")
      (node (ref "A1") (pin "14") (pinfunction "MOSI/CFGC0_14") (pintype "bidirectional"))
      (node (ref "R8") (pin "1") (pinfunction "1_1") (pintype "passive"))
    )
    (net (code "28") (name "Net-(A1-RFIN)") (class "Default")
      (node (ref "A1") (pin "11") (pinfunction "RFIN_11") (pintype "bidirectional"))
      (node (ref "L3") (pin "1") (pinfunction "1_1") (pintype "passive"))
      (node (ref "X4") (pin "SIG") (pinfunction "2_SIG") (pintype "passive"))
    )
    (net (code "29") (name "Net-(A1-VCCRF1)") (class "Default")
      (node (ref "A1") (pin "8") (pinfunction "VCCRF1_8") (pintype "bidirectional"))
      (node (ref "A1") (pin "9") (pinfunction "VCCRF2_9") (pintype "bidirectional"))
      (node (ref "R7") (pin "2") (pinfunction "2_2") (pintype "passive"))
    )
    (net (code "30") (name "Net-(D1A-BOOT0)") (class "Default")
      (node (ref "D1") (pin "60") (pinfunction "BOOT0_60") (pintype "bidirectional"))
      (node (ref "R19") (pin "2") (pinfunction "2_2") (pintype "passive"))
    )
    (net (code "31") (name "Net-(D1A-PA13{slash}TMS{slash}SWDIO)") (class "Default")
      (node (ref "D1") (pin "46") (pinfunction "PA13/TMS/SWDIO_46") (pintype "bidirectional"))
      (node (ref "R42") (pin "2") (pinfunction "2_2") (pintype "passive"))
    )
    (net (code "32") (name "Net-(D1A-PA14{slash}TCK{slash}SWCLK)") (class "Default")
      (node (ref "D1") (pin "49") (pinfunction "PA14/TCK/SWCLK_49") (pintype "bidirectional"))
      (node (ref "R47") (pin "2") (pinfunction "2_2") (pintype "passive"))
    )
    (net (code "33") (name "Net-(D1A-PB2{slash}BOOT1)") (class "Default")
      (node (ref "D1") (pin "28") (pinfunction "PB2/BOOT1_28") (pintype "bidirectional"))
      (node (ref "R20") (pin "2") (pinfunction "2_2") (pintype "passive"))
    )
    (net (code "34") (name "Net-(D1A-PH0{slash}OSCIN)") (class "Default")
      (node (ref "C23") (pin "1") (pinfunction "1_1") (pintype "passive"))
      (node (ref "D1") (pin "5") (pinfunction "PH0/OSCIN_5") (pintype "bidirectional"))
      (node (ref "G1") (pin "1") (pinfunction "X1_1") (pintype "bidirectional"))
    )
    (net (code "35") (name "Net-(D1A-PH1{slash}OSCOUT)") (class "Default")
      (node (ref "C24") (pin "1") (pinfunction "1_1") (pintype "passive"))
      (node (ref "D1") (pin "6") (pinfunction "PH1/OSCOUT_6") (pintype "bidirectional"))
      (node (ref "G1") (pin "3") (pinfunction "X2_3") (pintype "bidirectional"))
    )
    (net (code "36") (name "Net-(D1A-VCAP1)") (class "Default")
      (node (ref "C9") (pin "1") (pinfunction "1_1") (pintype "passive"))
      (node (ref "D1") (pin "30") (pinfunction "VCAP1_30") (pintype "bidirectional"))
    )
    (net (code "37") (name "Net-(D1A-VDDA{slash}VREF+)") (class "Default")
      (node (ref "C12") (pin "1") (pinfunction "1_1") (pintype "passive"))
      (node (ref "C17") (pin "1") (pinfunction "1_1") (pintype "passive"))
      (node (ref "D1") (pin "13") (pinfunction "VDDA/VREF+_13") (pintype "bidirectional"))
      (node (ref "L2") (pin "1") (pinfunction "1_1") (pintype "passive"))
    )
    (net (code "38") (name "Net-(F1-Pad1)") (class "Default")
      (node (ref "F1") (pin "1") (pinfunction "1_1") (pintype "passive"))
      (node (ref "X1") (pin "2") (pinfunction "2_2") (pintype "passive"))
    )
    (net (code "39") (name "Net-(H1-PadC)") (class "Default")
      (node (ref "H1") (pin "C") (pinfunction "C_C") (pintype "passive"))
      (node (ref "R6") (pin "2") (pinfunction "2_2") (pintype "passive"))
    )
    (net (code "40") (name "Net-(H2-PadC)") (class "Default")
      (node (ref "H2") (pin "C") (pinfunction "C_C") (pintype "passive"))
      (node (ref "R22") (pin "2") (pinfunction "2_2") (pintype "passive"))
    )
    (net (code "41") (name "Net-(H3-PadC)") (class "Default")
      (node (ref "H3") (pin "C") (pinfunction "C_C") (pintype "passive"))
      (node (ref "R23") (pin "2") (pinfunction "2_2") (pintype "passive"))
    )
    (net (code "42") (name "Net-(H4-PadC)") (class "Default")
      (node (ref "H4") (pin "C") (pinfunction "C_C") (pintype "passive"))
      (node (ref "R26") (pin "2") (pinfunction "2_2") (pintype "passive"))
    )
    (net (code "43") (name "Net-(L3-Pad2)") (class "Default")
      (node (ref "L3") (pin "2") (pinfunction "2_2") (pintype "passive"))
      (node (ref "R7") (pin "1") (pinfunction "1_1") (pintype "passive"))
    )
    (net (code "44") (name "Net-(N1-PH)") (class "Default")
      (node (ref "L1") (pin "2") (pinfunction "2_2") (pintype "passive"))
      (node (ref "N1") (pin "3") (pinfunction "PH_3") (pintype "bidirectional"))
    )
    (net (code "45") (name "Net-(N1-SENSE)") (class "Default")
      (node (ref "N1") (pin "5") (pinfunction "SENSE_5") (pintype "bidirectional"))
      (node (ref "R1") (pin "2") (pinfunction "2_2") (pintype "passive"))
      (node (ref "R2") (pin "1") (pinfunction "1_1") (pintype "passive"))
    )
    (net (code "46") (name "Net-(V2A-D-Pad5)") (class "Default")
      (node (ref "V2") (pin "5") (pinfunction "D_5") (pintype "passive"))
      (node (ref "V2") (pin "6") (pinfunction "D_6") (pintype "passive"))
      (node (ref "V8") (pin "A") (pinfunction "A_A") (pintype "passive"))
    )
    (net (code "47") (name "Net-(V2A-G)") (class "Default")
      (node (ref "R12") (pin "1") (pinfunction "1_1") (pintype "passive"))
      (node (ref "V2") (pin "4") (pinfunction "G_4") (pintype "passive"))
      (node (ref "V3") (pin "3") (pinfunction "D_3") (pintype "passive"))
    )
    (net (code "48") (name "Net-(V2B-G)") (class "Default")
      (node (ref "R3") (pin "1") (pinfunction "1_1") (pintype "passive"))
      (node (ref "V2") (pin "2") (pinfunction "G_2") (pintype "passive"))
      (node (ref "V5") (pin "3") (pinfunction "D_3") (pintype "passive"))
    )
    (net (code "49") (name "Net-(V10-PadA)") (class "Default")
      (node (ref "V10") (pin "A") (pinfunction "A_A") (pintype "passive"))
      (node (ref "V2") (pin "7") (pinfunction "D_7") (pintype "passive"))
      (node (ref "V2") (pin "8") (pinfunction "D_8") (pintype "passive"))
    )
    (net (code "50") (name "OUT1") (class "Default")
      (node (ref "D1") (pin "24") (pinfunction "PC4_24") (pintype "bidirectional"))
      (node (ref "R11") (pin "1") (pinfunction "1_1") (pintype "passive"))
      (node (ref "V3") (pin "1") (pinfunction "G_1") (pintype "passive"))
    )
    (net (code "51") (name "OUT2") (class "Default")
      (node (ref "D1") (pin "25") (pinfunction "PC5_25") (pintype "bidirectional"))
      (node (ref "R13") (pin "1") (pinfunction "1_1") (pintype "passive"))
      (node (ref "V5") (pin "1") (pinfunction "G_1") (pintype "passive"))
    )
    (net (code "52") (name "RESETL") (class "Default")
      (node (ref "D1") (pin "7") (pinfunction "RSTL_7") (pintype "bidirectional"))
      (node (ref "D10") (pin "1") (pinfunction "RESET_1") (pintype "bidirectional"))
      (node (ref "R16") (pin "1") (pinfunction "1_1") (pintype "passive"))
      (node (ref "X5") (pin "5") (pinfunction "5_5") (pintype "passive"))
    )
    (net (code "53") (name "SPI2CLK") (class "Default")
      (node (ref "D1") (pin "34") (pinfunction "PB13_34") (pintype "bidirectional"))
      (node (ref "D4") (pin "6") (pinfunction "SCLK_6") (pintype "bidirectional"))
    )
    (net (code "54") (name "SPI2CSN") (class "Default")
      (node (ref "D1") (pin "33") (pinfunction "PB12_33") (pintype "bidirectional"))
      (node (ref "D4") (pin "1") (pinfunction "CSN_1") (pintype "bidirectional"))
      (node (ref "R18") (pin "1") (pinfunction "1_1") (pintype "passive"))
    )
    (net (code "55") (name "SPI2MISO") (class "Default")
      (node (ref "D1") (pin "35") (pinfunction "PB14_35") (pintype "bidirectional"))
      (node (ref "D4") (pin "2") (pinfunction "SO_IO1_2") (pintype "bidirectional"))
    )
    (net (code "56") (name "SPI2MOSI") (class "Default")
      (node (ref "D1") (pin "36") (pinfunction "PB15_36") (pintype "bidirectional"))
      (node (ref "D4") (pin "5") (pinfunction "SI_IO0_5") (pintype "bidirectional"))
    )
    (net (code "57") (name "SWCLK") (class "Default")
      (node (ref "R47") (pin "1") (pinfunction "1_1") (pintype "passive"))
      (node (ref "X5") (pin "3") (pinfunction "3_3") (pintype "passive"))
    )
    (net (code "58") (name "SWDIO") (class "Default")
      (node (ref "R42") (pin "1") (pinfunction "1_1") (pintype "passive"))
      (node (ref "X5") (pin "2") (pinfunction "2_2") (pintype "passive"))
    )
    (net (code "59") (name "USART6RX") (class "Default")
      (node (ref "D1") (pin "45") (pinfunction "PA12_45") (pintype "bidirectional"))
      (node (ref "X3") (pin "2") (pinfunction "2_2") (pintype "passive"))
    )
    (net (code "60") (name "USART6TX") (class "Default")
      (node (ref "D1") (pin "44") (pinfunction "PA11_44") (pintype "bidirectional"))
      (node (ref "X3") (pin "1") (pinfunction "1_1") (pintype "passive"))
    )
    (net (code "61") (name "unconnected-(A1-EXTINT0-Pad4)") (class "Default")
      (node (ref "A1") (pin "4") (pinfunction "EXTINT0_4") (pintype "bidirectional"))
    )
    (net (code "62") (name "unconnected-(A1-MISO{slash}CFGC1-Pad15)") (class "Default")
      (node (ref "A1") (pin "15") (pinfunction "MISO/CFGC1_15") (pintype "bidirectional"))
    )
    (net (code "63") (name "unconnected-(A1-NC1-Pad1)") (class "Default")
      (node (ref "A1") (pin "1") (pinfunction "NC1_1") (pintype "bidirectional"))
    )
    (net (code "64") (name "unconnected-(A1-NC2-Pad17)") (class "Default")
      (node (ref "A1") (pin "17") (pinfunction "NC2_17") (pintype "bidirectional"))
    )
    (net (code "65") (name "unconnected-(A1-SCK{slash}CFGG0-Pad16)") (class "Default")
      (node (ref "A1") (pin "16") (pinfunction "SCK/CFGG0_16") (pintype "bidirectional"))
    )
    (net (code "66") (name "unconnected-(A1-SS_N-Pad2)") (class "Default")
      (node (ref "A1") (pin "2") (pinfunction "SS_N_2") (pintype "bidirectional"))
    )
    (net (code "67") (name "unconnected-(A1-USBDM-Pad5)") (class "Default")
      (node (ref "A1") (pin "5") (pinfunction "USBDM_5") (pintype "bidirectional"))
    )
    (net (code "68") (name "unconnected-(A1-USBDP-Pad6)") (class "Default")
      (node (ref "A1") (pin "6") (pinfunction "USBDP_6") (pintype "bidirectional"))
    )
    (net (code "69") (name "unconnected-(D1A-PA15{slash}TDI-Pad50)") (class "Default")
      (node (ref "D1") (pin "50") (pinfunction "PA15/TDI_50") (pintype "bidirectional"))
    )
    (net (code "70") (name "unconnected-(D1A-PB3{slash}TDO-Pad55)") (class "Default")
      (node (ref "D1") (pin "55") (pinfunction "PB3/TDO_55") (pintype "bidirectional"))
    )
    (net (code "71") (name "unconnected-(D1A-PB4{slash}TRSTL-Pad56)") (class "Default")
      (node (ref "D1") (pin "56") (pinfunction "PB4/TRSTL_56") (pintype "bidirectional"))
    )
    (net (code "72") (name "unconnected-(D1A-PC14{slash}OSC32IN-Pad3)") (class "Default")
      (node (ref "D1") (pin "3") (pinfunction "PC14/OSC32IN_3") (pintype "bidirectional"))
    )
    (net (code "73") (name "unconnected-(D1A-PC15{slash}OSC32OUT-Pad4)") (class "Default")
      (node (ref "D1") (pin "4") (pinfunction "PC15/OSC32OUT_4") (pintype "bidirectional"))
    )
    (net (code "74") (name "unconnected-(D1B-PA4-Pad20)") (class "Default")
      (node (ref "D1") (pin "20") (pinfunction "PA4_20") (pintype "bidirectional"))
    )
    (net (code "75") (name "unconnected-(D1B-PA5-Pad21)") (class "Default")
      (node (ref "D1") (pin "21") (pinfunction "PA5_21") (pintype "bidirectional"))
    )
    (net (code "76") (name "unconnected-(D1B-PA6-Pad22)") (class "Default")
      (node (ref "D1") (pin "22") (pinfunction "PA6_22") (pintype "bidirectional"))
    )
    (net (code "77") (name "unconnected-(D1B-PA7-Pad23)") (class "Default")
      (node (ref "D1") (pin "23") (pinfunction "PA7_23") (pintype "bidirectional"))
    )
    (net (code "78") (name "unconnected-(D1B-PB0-Pad26)") (class "Default")
      (node (ref "D1") (pin "26") (pinfunction "PB0_26") (pintype "bidirectional"))
    )
    (net (code "79") (name "unconnected-(D1B-PB1-Pad27)") (class "Default")
      (node (ref "D1") (pin "27") (pinfunction "PB1_27") (pintype "bidirectional"))
    )
    (net (code "80") (name "unconnected-(D1B-PB5-Pad57)") (class "Default")
      (node (ref "D1") (pin "57") (pinfunction "PB5_57") (pintype "bidirectional"))
    )
    (net (code "81") (name "unconnected-(D1B-PB8-Pad61)") (class "Default")
      (node (ref "D1") (pin "61") (pinfunction "PB8_61") (pintype "bidirectional"))
    )
    (net (code "82") (name "unconnected-(D1B-PB9-Pad62)") (class "Default")
      (node (ref "D1") (pin "62") (pinfunction "PB9_62") (pintype "bidirectional"))
    )
    (net (code "83") (name "unconnected-(D1B-PB10-Pad29)") (class "Default")
      (node (ref "D1") (pin "29") (pinfunction "PB10_29") (pintype "bidirectional"))
    )
    (net (code "84") (name "unconnected-(D1B-PB11-Pad54)") (class "Default")
      (node (ref "D1") (pin "54") (pinfunction "PB11_54") (pintype "bidirectional"))
    )
    (net (code "85") (name "unconnected-(D1B-PC6-Pad37)") (class "Default")
      (node (ref "D1") (pin "37") (pinfunction "PC6_37") (pintype "bidirectional"))
    )
    (net (code "86") (name "unconnected-(D1B-PC7-Pad38)") (class "Default")
      (node (ref "D1") (pin "38") (pinfunction "PC7_38") (pintype "bidirectional"))
    )
    (net (code "87") (name "unconnected-(D1B-PC10-Pad51)") (class "Default")
      (node (ref "D1") (pin "51") (pinfunction "PC10_51") (pintype "bidirectional"))
    )
    (net (code "88") (name "unconnected-(D1B-PC11-Pad52)") (class "Default")
      (node (ref "D1") (pin "52") (pinfunction "PC11_52") (pintype "bidirectional"))
    )
    (net (code "89") (name "unconnected-(D1B-PC12-Pad53)") (class "Default")
      (node (ref "D1") (pin "53") (pinfunction "PC12_53") (pintype "bidirectional"))
    )
    (net (code "90") (name "unconnected-(D1B-PC13-Pad2)") (class "Default")
      (node (ref "D1") (pin "2") (pinfunction "PC13_2") (pintype "bidirectional"))
    )
    (net (code "91") (name "unconnected-(D3-OS-Pad3)") (class "Default")
      (node (ref "D3") (pin "3") (pinfunction "OS_3") (pintype "bidirectional"))
    )
    (net (code "92") (name "unconnected-(D4-HOLDN_IO3-Pad7)") (class "Default")
      (node (ref "D4") (pin "7") (pinfunction "HOLDN_IO3_7") (pintype "bidirectional"))
    )
    (net (code "93") (name "unconnected-(D4-WPN_IO2-Pad3)") (class "Default")
      (node (ref "D4") (pin "3") (pinfunction "WPN_IO2_3") (pintype "bidirectional"))
    )
    (net (code "94") (name "unconnected-(D5-WP-Pad7)") (class "Default")
      (node (ref "D5") (pin "7") (pinfunction "WP_7") (pintype "input"))
    )
    (net (code "95") (name "unconnected-(N1-ENA-Pad1)") (class "Default")
      (node (ref "N1") (pin "1") (pinfunction "ENA_1") (pintype "bidirectional"))
    )
  )
)
